# EVK-IRIS-W1-FTDI.net
KiCad netlist of a schematic drawn in Altium Designer
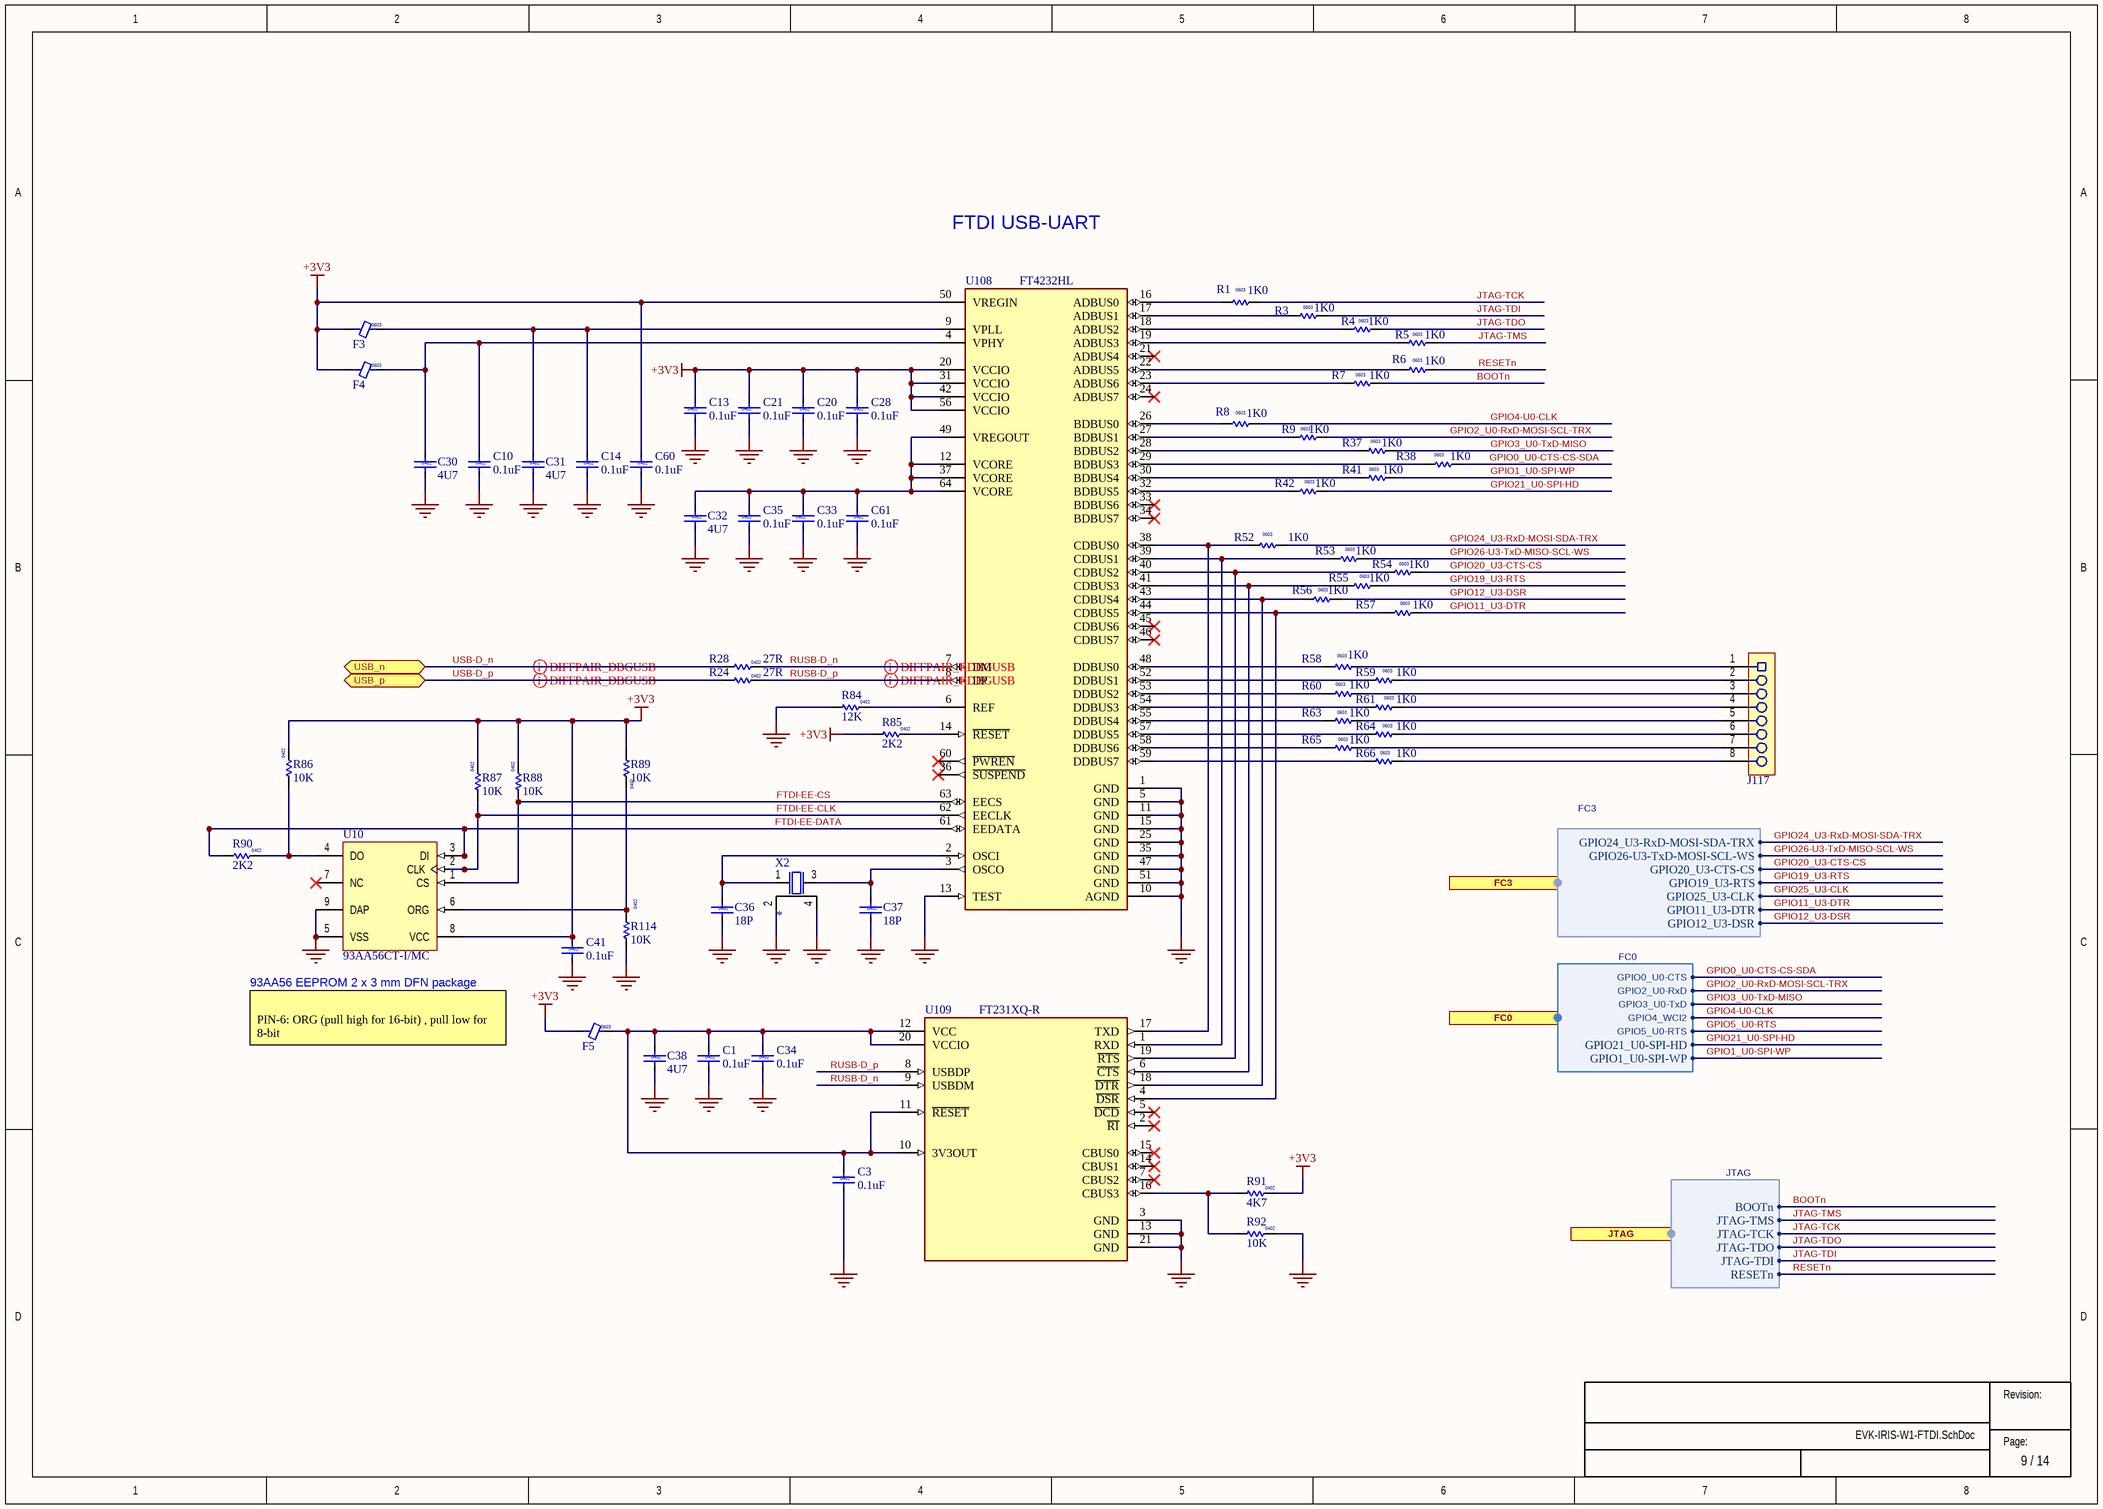
[diagram p0: EVK-IRIS-W1-FTDI.SchDoc]

(export (version "E")
  (design (tool "Eeschema 10.0.6"))
  (components
    (comp (ref "C1")
      (value "0.1uF")
      (footprint "Cap 0402 HD")
      (description "Cap, Ceramic 0.1uF 10V 10% X5R 0402")
      (fields
        (field (name "SIZE") "0402")
        (field (name "PART NUMBER") "120-00016")
        (field (name "TOLERANCE") "+/- 10%")
      )
      (libsource (lib "Arena_Parts_DB_Lib") (part "Cap Chip"))
    )
    (comp (ref "C3")
      (value "0.1uF")
      (footprint "Cap 0402 HD")
      (description "Cap, Ceramic 0.1uF 10V 10% X5R 0402")
      (fields
        (field (name "SIZE") "0402")
        (field (name "PART NUMBER") "120-00016")
        (field (name "TOLERANCE") "+/- 10%")
      )
      (libsource (lib "Arena_Parts_DB_Lib") (part "Cap Chip"))
    )
    (comp (ref "C10")
      (value "0.1uF")
      (footprint "Cap 0402 HD")
      (description "Cap, Ceramic 0.1uF 10V 10% X5R 0402")
      (fields
        (field (name "SIZE") "0402")
        (field (name "PART NUMBER") "120-00016")
        (field (name "TOLERANCE") "+/- 10%")
      )
      (libsource (lib "Arena_Parts_DB_Lib") (part "Cap Chip"))
    )
    (comp (ref "C13")
      (value "0.1uF")
      (footprint "Cap 0402 HD")
      (description "Cap, Ceramic 0.1uF 10V 10% X5R 0402")
      (fields
        (field (name "SIZE") "0402")
        (field (name "PART NUMBER") "120-00016")
        (field (name "TOLERANCE") "+/- 10%")
      )
      (libsource (lib "Arena_Parts_DB_Lib") (part "Cap Chip"))
    )
    (comp (ref "C14")
      (value "0.1uF")
      (footprint "Cap 0402 HD")
      (description "Cap, Ceramic 0.1uF 10V 10% X5R 0402")
      (fields
        (field (name "SIZE") "0402")
        (field (name "PART NUMBER") "120-00016")
        (field (name "TOLERANCE") "+/- 10%")
      )
      (libsource (lib "Arena_Parts_DB_Lib") (part "Cap Chip"))
    )
    (comp (ref "C20")
      (value "0.1uF")
      (footprint "Cap 0402 HD")
      (description "Cap, Ceramic 0.1uF 10V 10% X5R 0402")
      (fields
        (field (name "SIZE") "0402")
        (field (name "PART NUMBER") "120-00016")
        (field (name "TOLERANCE") "+/- 10%")
      )
      (libsource (lib "Arena_Parts_DB_Lib") (part "Cap Chip"))
    )
    (comp (ref "C21")
      (value "0.1uF")
      (footprint "Cap 0402 HD")
      (description "Cap, Ceramic 0.1uF 10V 10% X5R 0402")
      (fields
        (field (name "SIZE") "0402")
        (field (name "PART NUMBER") "120-00016")
        (field (name "TOLERANCE") "+/- 10%")
      )
      (libsource (lib "Arena_Parts_DB_Lib") (part "Cap Chip"))
    )
    (comp (ref "C28")
      (value "0.1uF")
      (footprint "Cap 0402 HD")
      (description "Cap, Ceramic 0.1uF 10V 10% X5R 0402")
      (fields
        (field (name "SIZE") "0402")
        (field (name "PART NUMBER") "120-00016")
        (field (name "TOLERANCE") "+/- 10%")
      )
      (libsource (lib "Arena_Parts_DB_Lib") (part "Cap Chip"))
    )
    (comp (ref "C30")
      (value "4U7")
      (footprint "Cap 0402 HD")
      (description "CAP CER X5R 0402 4U7 20% 10V")
      (fields
        (field (name "SIZE") "0402")
        (field (name "PART NUMBER") "UBXH01-0000243")
        (field (name "TOLERANCE") "20%")
        (field (name "EDITOR") "martin.pilik")
        (field (name "RELEASED BY") "fabrice.bret-dibat")
      )
      (libsource (lib "UBX_Parts_DB_Lib") (part "Cap Chip"))
    )
    (comp (ref "C31")
      (value "4U7")
      (footprint "Cap 0402 HD")
      (description "CAP CER X5R 0402 4U7 20% 10V")
      (fields
        (field (name "SIZE") "0402")
        (field (name "PART NUMBER") "UBXH01-0000243")
        (field (name "TOLERANCE") "20%")
        (field (name "EDITOR") "martin.pilik")
        (field (name "RELEASED BY") "fabrice.bret-dibat")
      )
      (libsource (lib "UBX_Parts_DB_Lib") (part "Cap Chip"))
    )
    (comp (ref "C32")
      (value "4U7")
      (footprint "Cap 0402 HD")
      (description "CAP CER X5R 0402 4U7 20% 10V")
      (fields
        (field (name "SIZE") "0402")
        (field (name "PART NUMBER") "UBXH01-0000243")
        (field (name "TOLERANCE") "20%")
        (field (name "EDITOR") "martin.pilik")
        (field (name "RELEASED BY") "fabrice.bret-dibat")
      )
      (libsource (lib "UBX_Parts_DB_Lib") (part "Cap Chip"))
    )
    (comp (ref "C33")
      (value "0.1uF")
      (footprint "Cap 0402 HD")
      (description "Cap, Ceramic 0.1uF 10V 10% X5R 0402")
      (fields
        (field (name "SIZE") "0402")
        (field (name "PART NUMBER") "120-00016")
        (field (name "TOLERANCE") "+/- 10%")
      )
      (libsource (lib "Arena_Parts_DB_Lib") (part "Cap Chip"))
    )
    (comp (ref "C34")
      (value "0.1uF")
      (footprint "Cap 0402 HD")
      (description "Cap, Ceramic 0.1uF 10V 10% X5R 0402")
      (fields
        (field (name "SIZE") "0402")
        (field (name "PART NUMBER") "120-00016")
        (field (name "TOLERANCE") "+/- 10%")
      )
      (libsource (lib "Arena_Parts_DB_Lib") (part "Cap Chip"))
    )
    (comp (ref "C35")
      (value "0.1uF")
      (footprint "Cap 0402 HD")
      (description "Cap, Ceramic 0.1uF 10V 10% X5R 0402")
      (fields
        (field (name "SIZE") "0402")
        (field (name "PART NUMBER") "120-00016")
        (field (name "TOLERANCE") "+/- 10%")
      )
      (libsource (lib "Arena_Parts_DB_Lib") (part "Cap Chip"))
    )
    (comp (ref "C36")
      (value "18P")
      (footprint "Cap 0402")
      (description "CAP CER C0G 0402 18P 5% 25V")
      (fields
        (field (name "SIZE") "0402")
        (field (name "PART NUMBER") "UBXH01-0004017")
        (field (name "TOLERANCE") "5%")
        (field (name "EDITOR") "doris.zahnd")
        (field (name "RELEASED BY") "daniel.hurni")
      )
      (libsource (lib "UBX_Parts_DB_Lib") (part "Cap Chip"))
    )
    (comp (ref "C37")
      (value "18P")
      (footprint "Cap 0402")
      (description "CAP CER C0G 0402 18P 5% 25V")
      (fields
        (field (name "SIZE") "0402")
        (field (name "PART NUMBER") "UBXH01-0004017")
        (field (name "TOLERANCE") "5%")
        (field (name "EDITOR") "doris.zahnd")
        (field (name "RELEASED BY") "daniel.hurni")
      )
      (libsource (lib "UBX_Parts_DB_Lib") (part "Cap Chip"))
    )
    (comp (ref "C38")
      (value "4U7")
      (footprint "Cap 0402 HD")
      (description "CAP CER X5R 0402 4U7 20% 10V")
      (fields
        (field (name "SIZE") "0402")
        (field (name "PART NUMBER") "UBXH01-0000243")
        (field (name "TOLERANCE") "20%")
        (field (name "EDITOR") "martin.pilik")
        (field (name "RELEASED BY") "fabrice.bret-dibat")
      )
      (libsource (lib "UBX_Parts_DB_Lib") (part "Cap Chip"))
    )
    (comp (ref "C41")
      (value "0.1uF")
      (footprint "Cap 0402 HD")
      (description "Cap, Ceramic 0.1uF 10V 10% X5R 0402")
      (fields
        (field (name "SIZE") "0402")
        (field (name "PART NUMBER") "120-00016")
        (field (name "TOLERANCE") "+/- 10%")
      )
      (libsource (lib "Arena_Parts_DB_Lib") (part "Cap Chip"))
    )
    (comp (ref "C60")
      (value "0.1uF")
      (footprint "Cap 0402 HD")
      (description "Cap, Ceramic 0.1uF 10V 10% X5R 0402")
      (fields
        (field (name "SIZE") "0402")
        (field (name "PART NUMBER") "120-00016")
        (field (name "TOLERANCE") "+/- 10%")
      )
      (libsource (lib "Arena_Parts_DB_Lib") (part "Cap Chip"))
    )
    (comp (ref "C61")
      (value "0.1uF")
      (footprint "Cap 0402 HD")
      (description "Cap, Ceramic 0.1uF 10V 10% X5R 0402")
      (fields
        (field (name "SIZE") "0402")
        (field (name "PART NUMBER") "120-00016")
        (field (name "TOLERANCE") "+/- 10%")
      )
      (libsource (lib "Arena_Parts_DB_Lib") (part "Cap Chip"))
    )
    (comp (ref "F3")
      (value "UBXH08-0000001")
      (footprint "IND 0603 HD")
      (description "FERRITE BEAD 0603 600 OHM AT 100MHZ 600OHM 500mA")
      (fields
        (field (name "SIZE") "0603")
        (field (name "MANUFACTURER") "TDK Corporation")
        (field (name "EDITOR") "daniel.hurni")
        (field (name "RELEASED BY") "martin.frauchiger")
      )
      (libsource (lib "UBX_Parts_DB_Lib") (part "FB sm"))
    )
    (comp (ref "F4")
      (value "UBXH08-0000001")
      (footprint "IND 0603 HD")
      (description "FERRITE BEAD 0603 600 OHM AT 100MHZ 600OHM 500mA")
      (fields
        (field (name "SIZE") "0603")
        (field (name "MANUFACTURER") "TDK Corporation")
        (field (name "EDITOR") "daniel.hurni")
        (field (name "RELEASED BY") "martin.frauchiger")
      )
      (libsource (lib "UBX_Parts_DB_Lib") (part "FB sm"))
    )
    (comp (ref "F5")
      (value "UBXH08-0000001")
      (footprint "IND 0603 HD")
      (description "FERRITE BEAD 0603 600 OHM AT 100MHZ 600OHM 500mA")
      (fields
        (field (name "SIZE") "0603")
        (field (name "MANUFACTURER") "TDK Corporation")
        (field (name "EDITOR") "daniel.hurni")
        (field (name "RELEASED BY") "martin.frauchiger")
      )
      (libsource (lib "UBX_Parts_DB_Lib") (part "FB sm"))
    )
    (comp (ref "J117")
      (value "130-00102")
      (footprint "SKT-0.1P-SSM-108-L-SV")
      (description "Socket Strip 0.1\" 8 Pin 1Row SMD Black")
      (fields (field (name "VOLTAGE") "572VDC"))
      (libsource (lib "Arena_Parts_DB_Lib") (part "CON-8Pin_1Row"))
    )
    (comp (ref "R1")
      (value "1K0")
      (footprint "RES 0603 HD")
      (description "RES THICK FILM CHIP 0603 25PPM 1K0 0.1% 100mW")
      (fields
        (field (name "SIZE") "0603")
        (field (name "PART NUMBER") "UBXH18-0000400")
        (field (name "TOLERANCE") "0.1%")
        (field (name "EDITOR") "martin.kessel")
      )
      (libsource (lib "UBX_Parts_DB_Lib") (part "Res sm"))
    )
    (comp (ref "R3")
      (value "1K0")
      (footprint "RES 0603 HD")
      (description "RES THICK FILM CHIP 0603 25PPM 1K0 0.1% 100mW")
      (fields
        (field (name "SIZE") "0603")
        (field (name "PART NUMBER") "UBXH18-0000400")
        (field (name "TOLERANCE") "0.1%")
        (field (name "EDITOR") "martin.kessel")
      )
      (libsource (lib "UBX_Parts_DB_Lib") (part "Res sm"))
    )
    (comp (ref "R4")
      (value "1K0")
      (footprint "RES 0603 HD")
      (description "RES THICK FILM CHIP 0603 25PPM 1K0 0.1% 100mW")
      (fields
        (field (name "SIZE") "0603")
        (field (name "PART NUMBER") "UBXH18-0000400")
        (field (name "TOLERANCE") "0.1%")
        (field (name "EDITOR") "martin.kessel")
      )
      (libsource (lib "UBX_Parts_DB_Lib") (part "Res sm"))
    )
    (comp (ref "R5")
      (value "1K0")
      (footprint "RES 0603 HD")
      (description "RES THICK FILM CHIP 0603 25PPM 1K0 0.1% 100mW")
      (fields
        (field (name "SIZE") "0603")
        (field (name "PART NUMBER") "UBXH18-0000400")
        (field (name "TOLERANCE") "0.1%")
        (field (name "EDITOR") "martin.kessel")
      )
      (libsource (lib "UBX_Parts_DB_Lib") (part "Res sm"))
    )
    (comp (ref "R6")
      (value "1K0")
      (footprint "RES 0603 HD")
      (description "RES THICK FILM CHIP 0603 25PPM 1K0 0.1% 100mW")
      (fields
        (field (name "SIZE") "0603")
        (field (name "PART NUMBER") "UBXH18-0000400")
        (field (name "TOLERANCE") "0.1%")
        (field (name "EDITOR") "martin.kessel")
      )
      (libsource (lib "UBX_Parts_DB_Lib") (part "Res sm"))
    )
    (comp (ref "R7")
      (value "1K0")
      (footprint "RES 0603 HD")
      (description "RES THICK FILM CHIP 0603 25PPM 1K0 0.1% 100mW")
      (fields
        (field (name "SIZE") "0603")
        (field (name "PART NUMBER") "UBXH18-0000400")
        (field (name "TOLERANCE") "0.1%")
        (field (name "EDITOR") "martin.kessel")
      )
      (libsource (lib "UBX_Parts_DB_Lib") (part "Res sm"))
    )
    (comp (ref "R8")
      (value "1K0")
      (footprint "RES 0603 HD")
      (description "RES THICK FILM CHIP 0603 25PPM 1K0 0.1% 100mW")
      (fields
        (field (name "SIZE") "0603")
        (field (name "PART NUMBER") "UBXH18-0000400")
        (field (name "TOLERANCE") "0.1%")
        (field (name "EDITOR") "martin.kessel")
      )
      (libsource (lib "UBX_Parts_DB_Lib") (part "Res sm"))
    )
    (comp (ref "R9")
      (value "1K0")
      (footprint "RES 0603 HD")
      (description "RES THICK FILM CHIP 0603 25PPM 1K0 0.1% 100mW")
      (fields
        (field (name "SIZE") "0603")
        (field (name "PART NUMBER") "UBXH18-0000400")
        (field (name "TOLERANCE") "0.1%")
        (field (name "EDITOR") "martin.kessel")
      )
      (libsource (lib "UBX_Parts_DB_Lib") (part "Res sm"))
    )
    (comp (ref "R24")
      (value "27R")
      (footprint "RES 0402 HD")
      (description "Resistor, 27ohm, 1%, 1/16W, 0402")
      (fields
        (field (name "SIZE") "0402")
        (field (name "PART NUMBER") "180-00125")
        (field (name "POWER") "1/16W")
      )
      (libsource (lib "Arena_Parts_DB_Lib") (part "Res sm"))
    )
    (comp (ref "R28")
      (value "27R")
      (footprint "RES 0402 HD")
      (description "Resistor, 27ohm, 1%, 1/16W, 0402")
      (fields
        (field (name "SIZE") "0402")
        (field (name "PART NUMBER") "180-00125")
        (field (name "POWER") "1/16W")
      )
      (libsource (lib "Arena_Parts_DB_Lib") (part "Res sm"))
    )
    (comp (ref "R37")
      (value "1K0")
      (footprint "RES 0603 HD")
      (description "RES THICK FILM CHIP 0603 25PPM 1K0 0.1% 100mW")
      (fields
        (field (name "SIZE") "0603")
        (field (name "PART NUMBER") "UBXH18-0000400")
        (field (name "TOLERANCE") "0.1%")
        (field (name "EDITOR") "martin.kessel")
      )
      (libsource (lib "UBX_Parts_DB_Lib") (part "Res sm"))
    )
    (comp (ref "R38")
      (value "1K0")
      (footprint "RES 0603 HD")
      (description "RES THICK FILM CHIP 0603 25PPM 1K0 0.1% 100mW")
      (fields
        (field (name "SIZE") "0603")
        (field (name "PART NUMBER") "UBXH18-0000400")
        (field (name "TOLERANCE") "0.1%")
        (field (name "EDITOR") "martin.kessel")
      )
      (libsource (lib "UBX_Parts_DB_Lib") (part "Res sm"))
    )
    (comp (ref "R41")
      (value "1K0")
      (footprint "RES 0603 HD")
      (description "RES THICK FILM CHIP 0603 25PPM 1K0 0.1% 100mW")
      (fields
        (field (name "SIZE") "0603")
        (field (name "PART NUMBER") "UBXH18-0000400")
        (field (name "TOLERANCE") "0.1%")
        (field (name "EDITOR") "martin.kessel")
      )
      (libsource (lib "UBX_Parts_DB_Lib") (part "Res sm"))
    )
    (comp (ref "R42")
      (value "1K0")
      (footprint "RES 0603 HD")
      (description "RES THICK FILM CHIP 0603 25PPM 1K0 0.1% 100mW")
      (fields
        (field (name "SIZE") "0603")
        (field (name "PART NUMBER") "UBXH18-0000400")
        (field (name "TOLERANCE") "0.1%")
        (field (name "EDITOR") "martin.kessel")
      )
      (libsource (lib "UBX_Parts_DB_Lib") (part "Res sm"))
    )
    (comp (ref "R52")
      (value "1K0")
      (footprint "RES 0603 HD")
      (description "RES THICK FILM CHIP 0603 25PPM 1K0 0.1% 100mW")
      (fields
        (field (name "SIZE") "0603")
        (field (name "PART NUMBER") "UBXH18-0000400")
        (field (name "TOLERANCE") "0.1%")
        (field (name "EDITOR") "martin.kessel")
      )
      (libsource (lib "UBX_Parts_DB_Lib") (part "Res sm"))
    )
    (comp (ref "R53")
      (value "1K0")
      (footprint "RES 0603 HD")
      (description "RES THICK FILM CHIP 0603 25PPM 1K0 0.1% 100mW")
      (fields
        (field (name "SIZE") "0603")
        (field (name "PART NUMBER") "UBXH18-0000400")
        (field (name "TOLERANCE") "0.1%")
        (field (name "EDITOR") "martin.kessel")
      )
      (libsource (lib "UBX_Parts_DB_Lib") (part "Res sm"))
    )
    (comp (ref "R54")
      (value "1K0")
      (footprint "RES 0603 HD")
      (description "RES THICK FILM CHIP 0603 25PPM 1K0 0.1% 100mW")
      (fields
        (field (name "SIZE") "0603")
        (field (name "PART NUMBER") "UBXH18-0000400")
        (field (name "TOLERANCE") "0.1%")
        (field (name "EDITOR") "martin.kessel")
      )
      (libsource (lib "UBX_Parts_DB_Lib") (part "Res sm"))
    )
    (comp (ref "R55")
      (value "1K0")
      (footprint "RES 0603 HD")
      (description "RES THICK FILM CHIP 0603 25PPM 1K0 0.1% 100mW")
      (fields
        (field (name "SIZE") "0603")
        (field (name "PART NUMBER") "UBXH18-0000400")
        (field (name "TOLERANCE") "0.1%")
        (field (name "EDITOR") "martin.kessel")
      )
      (libsource (lib "UBX_Parts_DB_Lib") (part "Res sm"))
    )
    (comp (ref "R56")
      (value "1K0")
      (footprint "RES 0603 HD")
      (description "RES THICK FILM CHIP 0603 25PPM 1K0 0.1% 100mW")
      (fields
        (field (name "SIZE") "0603")
        (field (name "PART NUMBER") "UBXH18-0000400")
        (field (name "TOLERANCE") "0.1%")
        (field (name "EDITOR") "martin.kessel")
      )
      (libsource (lib "UBX_Parts_DB_Lib") (part "Res sm"))
    )
    (comp (ref "R57")
      (value "1K0")
      (footprint "RES 0603 HD")
      (description "RES THICK FILM CHIP 0603 25PPM 1K0 0.1% 100mW")
      (fields
        (field (name "SIZE") "0603")
        (field (name "PART NUMBER") "UBXH18-0000400")
        (field (name "TOLERANCE") "0.1%")
        (field (name "EDITOR") "martin.kessel")
      )
      (libsource (lib "UBX_Parts_DB_Lib") (part "Res sm"))
    )
    (comp (ref "R58")
      (value "1K0")
      (footprint "RES 0603 HD")
      (description "RES THICK FILM CHIP 0603 25PPM 1K0 0.1% 100mW")
      (fields
        (field (name "SIZE") "0603")
        (field (name "PART NUMBER") "UBXH18-0000400")
        (field (name "TOLERANCE") "0.1%")
        (field (name "EDITOR") "martin.kessel")
      )
      (libsource (lib "UBX_Parts_DB_Lib") (part "Res sm"))
    )
    (comp (ref "R59")
      (value "1K0")
      (footprint "RES 0603 HD")
      (description "RES THICK FILM CHIP 0603 25PPM 1K0 0.1% 100mW")
      (fields
        (field (name "SIZE") "0603")
        (field (name "PART NUMBER") "UBXH18-0000400")
        (field (name "TOLERANCE") "0.1%")
        (field (name "EDITOR") "martin.kessel")
      )
      (libsource (lib "UBX_Parts_DB_Lib") (part "Res sm"))
    )
    (comp (ref "R60")
      (value "1K0")
      (footprint "RES 0603 HD")
      (description "RES THICK FILM CHIP 0603 25PPM 1K0 0.1% 100mW")
      (fields
        (field (name "SIZE") "0603")
        (field (name "PART NUMBER") "UBXH18-0000400")
        (field (name "TOLERANCE") "0.1%")
        (field (name "EDITOR") "martin.kessel")
      )
      (libsource (lib "UBX_Parts_DB_Lib") (part "Res sm"))
    )
    (comp (ref "R61")
      (value "1K0")
      (footprint "RES 0603 HD")
      (description "RES THICK FILM CHIP 0603 25PPM 1K0 0.1% 100mW")
      (fields
        (field (name "SIZE") "0603")
        (field (name "PART NUMBER") "UBXH18-0000400")
        (field (name "TOLERANCE") "0.1%")
        (field (name "EDITOR") "martin.kessel")
      )
      (libsource (lib "UBX_Parts_DB_Lib") (part "Res sm"))
    )
    (comp (ref "R63")
      (value "1K0")
      (footprint "RES 0603 HD")
      (description "RES THICK FILM CHIP 0603 25PPM 1K0 0.1% 100mW")
      (fields
        (field (name "SIZE") "0603")
        (field (name "PART NUMBER") "UBXH18-0000400")
        (field (name "TOLERANCE") "0.1%")
        (field (name "EDITOR") "martin.kessel")
      )
      (libsource (lib "UBX_Parts_DB_Lib") (part "Res sm"))
    )
    (comp (ref "R64")
      (value "1K0")
      (footprint "RES 0603 HD")
      (description "RES THICK FILM CHIP 0603 25PPM 1K0 0.1% 100mW")
      (fields
        (field (name "SIZE") "0603")
        (field (name "PART NUMBER") "UBXH18-0000400")
        (field (name "TOLERANCE") "0.1%")
        (field (name "EDITOR") "martin.kessel")
      )
      (libsource (lib "UBX_Parts_DB_Lib") (part "Res sm"))
    )
    (comp (ref "R65")
      (value "1K0")
      (footprint "RES 0603 HD")
      (description "RES THICK FILM CHIP 0603 25PPM 1K0 0.1% 100mW")
      (fields
        (field (name "SIZE") "0603")
        (field (name "PART NUMBER") "UBXH18-0000400")
        (field (name "TOLERANCE") "0.1%")
        (field (name "EDITOR") "martin.kessel")
      )
      (libsource (lib "UBX_Parts_DB_Lib") (part "Res sm"))
    )
    (comp (ref "R66")
      (value "1K0")
      (footprint "RES 0603 HD")
      (description "RES THICK FILM CHIP 0603 25PPM 1K0 0.1% 100mW")
      (fields
        (field (name "SIZE") "0603")
        (field (name "PART NUMBER") "UBXH18-0000400")
        (field (name "TOLERANCE") "0.1%")
        (field (name "EDITOR") "martin.kessel")
      )
      (libsource (lib "UBX_Parts_DB_Lib") (part "Res sm"))
    )
    (comp (ref "R84")
      (value "12K")
      (footprint "RES 0402 HD")
      (description "RES THICK FILM CHIP 0402 12K 1% 63mW")
      (fields
        (field (name "SIZE") "0402")
        (field (name "PART NUMBER") "UBXH18-0000137")
        (field (name "TOLERANCE") "1%")
        (field (name "EDITOR") "matej.budin")
        (field (name "RELEASED BY") "gabriele.capello")
      )
      (libsource (lib "UBX_Parts_DB_Lib") (part "Res sm"))
    )
    (comp (ref "R85")
      (value "2K2")
      (footprint "RES 0402 HD")
      (description "RES THICK FILM CHIP 0402 2K2 5% 100mW")
      (fields
        (field (name "SIZE") "0402")
        (field (name "PART NUMBER") "UBXH18-0008057")
        (field (name "TOLERANCE") "5%")
        (field (name "EDITOR") "roland.rust")
        (field (name "RELEASED BY") "roland.rust")
      )
      (libsource (lib "UBX_Parts_DB_Lib") (part "Res sm"))
    )
    (comp (ref "R86")
      (value "10K")
      (footprint "RES 0402 HD")
      (description "RES THICK FILM CHIP 0402 10K 5% 100mW")
      (fields
        (field (name "SIZE") "0402")
        (field (name "PART NUMBER") "UBXH18-0008073")
        (field (name "TOLERANCE") "5%")
        (field (name "EDITOR") "martin.frauchiger")
        (field (name "RELEASED BY") "martin.frauchiger")
      )
      (libsource (lib "UBX_Parts_DB_Lib") (part "Res sm"))
    )
    (comp (ref "R87")
      (value "10K")
      (footprint "RES 0402 HD")
      (description "RES THICK FILM CHIP 0402 10K 5% 100mW")
      (fields
        (field (name "SIZE") "0402")
        (field (name "PART NUMBER") "UBXH18-0008073")
        (field (name "TOLERANCE") "5%")
        (field (name "EDITOR") "martin.frauchiger")
        (field (name "RELEASED BY") "martin.frauchiger")
      )
      (libsource (lib "UBX_Parts_DB_Lib") (part "Res sm"))
    )
    (comp (ref "R88")
      (value "10K")
      (footprint "RES 0402 HD")
      (description "RES THICK FILM CHIP 0402 10K 5% 100mW")
      (fields
        (field (name "SIZE") "0402")
        (field (name "PART NUMBER") "UBXH18-0008073")
        (field (name "TOLERANCE") "5%")
        (field (name "EDITOR") "martin.frauchiger")
        (field (name "RELEASED BY") "martin.frauchiger")
      )
      (libsource (lib "UBX_Parts_DB_Lib") (part "Res sm"))
    )
    (comp (ref "R89")
      (value "10K")
      (footprint "RES 0402 HD")
      (description "RES THICK FILM CHIP 0402 10K 5% 100mW")
      (fields
        (field (name "SIZE") "0402")
        (field (name "PART NUMBER") "UBXH18-0008073")
        (field (name "TOLERANCE") "5%")
        (field (name "EDITOR") "martin.frauchiger")
        (field (name "RELEASED BY") "martin.frauchiger")
      )
      (libsource (lib "UBX_Parts_DB_Lib") (part "Res sm"))
    )
    (comp (ref "R90")
      (value "2K2")
      (footprint "RES 0402 HD")
      (description "RES THICK FILM CHIP 0402 2K2 5% 100mW")
      (fields
        (field (name "SIZE") "0402")
        (field (name "PART NUMBER") "UBXH18-0008057")
        (field (name "TOLERANCE") "5%")
        (field (name "EDITOR") "roland.rust")
        (field (name "RELEASED BY") "roland.rust")
      )
      (libsource (lib "UBX_Parts_DB_Lib") (part "Res sm"))
    )
    (comp (ref "R91")
      (value "4K7")
      (footprint "RES 0402 HD")
      (description "RES THICK FILM CHIP 0402 4K7 5% 100mW")
      (fields
        (field (name "SIZE") "0402")
        (field (name "PART NUMBER") "UBXH18-0008065")
        (field (name "TOLERANCE") "5%")
        (field (name "EDITOR") "martin.frauchiger")
        (field (name "RELEASED BY") "martin.frauchiger")
      )
      (libsource (lib "UBX_Parts_DB_Lib") (part "Res sm"))
    )
    (comp (ref "R92")
      (value "10K")
      (footprint "RES 0402 HD")
      (description "RES THICK FILM CHIP 0402 10K 5% 100mW")
      (fields
        (field (name "SIZE") "0402")
        (field (name "PART NUMBER") "UBXH18-0008073")
        (field (name "TOLERANCE") "5%")
        (field (name "EDITOR") "martin.frauchiger")
        (field (name "RELEASED BY") "martin.frauchiger")
      )
      (libsource (lib "UBX_Parts_DB_Lib") (part "Res sm"))
    )
    (comp (ref "R114")
      (value "10K")
      (footprint "RES 0402 HD")
      (description "RES THICK FILM CHIP 0402 10K 5% 100mW")
      (fields
        (field (name "SIZE") "0402")
        (field (name "PART NUMBER") "UBXH18-0008073")
        (field (name "TOLERANCE") "5%")
        (field (name "EDITOR") "martin.frauchiger")
        (field (name "RELEASED BY") "martin.frauchiger")
      )
      (libsource (lib "UBX_Parts_DB_Lib") (part "Res sm"))
    )
    (comp (ref "U10")
      (value "93AA56CT-I/MC")
      (footprint "DFN-MC8")
      (fields (field (name "MANUFACTURER") "Microchip"))
      (libsource (lib "93AA56CT-I") (part "MEM-SEEPROM-93AA46C-MC-9"))
    )
    (comp (ref "U108")
      (value "FT4232HL")
      (footprint "QFP0.5P16x16-64Pin_HD")
      (description "FTDI FT4232HL QUAD HIGH SPEED USB TO MULTIPURPOSE UART LQFP-64")
      (fields
        (field (name "PART NUMBER") "UBXH10-0000092")
        (field (name "MANUFACTURER") "FTDI Future Technology Devices International")
        (field (name "EDITOR") "olof.viklund")
        (field (name "RELEASED BY") "aneeb.sohail")
      )
      (libsource (lib "UBX_Parts_DB_Lib") (part "FT4232HL"))
    )
    (comp (ref "U109")
      (value "FT231XQ-R")
      (footprint "QFN_5x5_FT231XQ")
      (description "FTDI USB TO SERIAL FULL UART INTERFACE QFN20")
      (fields
        (field (name "PART NUMBER") "UBXH10-0000054")
        (field (name "MANUFACTURER") "FTDI Future Technology Devices International")
        (field (name "EDITOR") "adam.johansson")
        (field (name "RELEASED BY") "jaka.bevk")
      )
      (libsource (lib "UBX_Parts_DB_Lib") (part "FT231XQ-R"))
    )
    (comp (ref "X2")
      (value "100-00006")
      (footprint "XTAL_3225")
      (description "XTAL, 4Pin, 12.0000MHz, 18pF, 20ppm, 4Pins")
      (fields (field (name "ALTIUM_VALUE") "*") (field (name "VOLTAGE") "None"))
      (libsource (lib "Arena_Parts_DB_Lib") (part "XTAL_4Pin"))
    )
  )
  (nets
    (net (code "4") (name "+3V3") (class "Default")
      (node (ref "C13") (pin "1") (pinfunction "1_1") (pintype "passive"))
      (node (ref "C20") (pin "1") (pinfunction "1_1") (pintype "passive"))
      (node (ref "C21") (pin "1") (pinfunction "1_1") (pintype "passive"))
      (node (ref "C28") (pin "1") (pinfunction "1_1") (pintype "passive"))
      (node (ref "C41") (pin "1") (pinfunction "1_1") (pintype "passive"))
      (node (ref "C60") (pin "1") (pinfunction "1_1") (pintype "passive"))
      (node (ref "F3") (pin "1") (pinfunction "1_1") (pintype "passive"))
      (node (ref "F4") (pin "1") (pinfunction "1_1") (pintype "passive"))
      (node (ref "F5") (pin "1") (pinfunction "1_1") (pintype "passive"))
      (node (ref "R85") (pin "1") (pinfunction "1_1") (pintype "passive"))
      (node (ref "R86") (pin "2") (pinfunction "2_2") (pintype "passive"))
      (node (ref "R87") (pin "2") (pinfunction "2_2") (pintype "passive"))
      (node (ref "R88") (pin "2") (pinfunction "2_2") (pintype "passive"))
      (node (ref "R89") (pin "1") (pinfunction "1_1") (pintype "passive"))
      (node (ref "R91") (pin "2") (pinfunction "2_2") (pintype "passive"))
      (node (ref "U10") (pin "8") (pinfunction "VCC_8") (pintype "power_in"))
      (node (ref "U108") (pin "20") (pinfunction "VCCIO_20") (pintype "power_in"))
      (node (ref "U108") (pin "31") (pinfunction "VCCIO_31") (pintype "power_in"))
      (node (ref "U108") (pin "42") (pinfunction "VCCIO_42") (pintype "power_in"))
      (node (ref "U108") (pin "50") (pinfunction "VREGIN_50") (pintype "power_in"))
      (node (ref "U108") (pin "56") (pinfunction "VCCIO_56") (pintype "power_in"))
    )
    (net (code "5") (name "/BOOTn") (class "Default")
      (node (ref "R7") (pin "2") (pinfunction "2_2") (pintype "passive"))
    )
    (net (code "6") (name "/FTDI-EE-CLK") (class "Default")
      (node (ref "R87") (pin "1") (pinfunction "1_1") (pintype "passive"))
      (node (ref "U10") (pin "2") (pinfunction "CLK_2") (pintype "input"))
      (node (ref "U108") (pin "62") (pinfunction "EECLK_62") (pintype "output"))
    )
    (net (code "7") (name "/FTDI-EE-CS") (class "Default")
      (node (ref "R88") (pin "1") (pinfunction "1_1") (pintype "passive"))
      (node (ref "U10") (pin "1") (pinfunction "CS_1") (pintype "input"))
      (node (ref "U108") (pin "63") (pinfunction "EECS_63") (pintype "bidirectional"))
    )
    (net (code "8") (name "/FTDI-EE-DATA") (class "Default")
      (node (ref "R90") (pin "1") (pinfunction "1_1") (pintype "passive"))
      (node (ref "U10") (pin "3") (pinfunction "DI_3") (pintype "input"))
      (node (ref "U108") (pin "61") (pinfunction "EEDATA_61") (pintype "bidirectional"))
    )
    (net (code "9") (name "/GPIO0_U0-CTS-CS-SDA") (class "Default")
      (node (ref "R38") (pin "2") (pinfunction "2_2") (pintype "passive"))
    )
    (net (code "10") (name "/GPIO1_U0-SPI-WP") (class "Default")
      (node (ref "R41") (pin "2") (pinfunction "2_2") (pintype "passive"))
    )
    (net (code "11") (name "/GPIO2_U0-RxD-MOSI-SCL-TRX") (class "Default")
      (node (ref "R9") (pin "2") (pinfunction "2_2") (pintype "passive"))
    )
    (net (code "12") (name "/GPIO3_U0-TxD-MISO") (class "Default")
      (node (ref "R37") (pin "2") (pinfunction "2_2") (pintype "passive"))
    )
    (net (code "13") (name "/GPIO4-U0-CLK") (class "Default")
      (node (ref "R8") (pin "2") (pinfunction "2_2") (pintype "passive"))
    )
    (net (code "15") (name "/GPIO11_U3-DTR") (class "Default")
      (node (ref "R57") (pin "2") (pinfunction "2_2") (pintype "passive"))
    )
    (net (code "16") (name "/GPIO12_U3-DSR") (class "Default")
      (node (ref "R56") (pin "2") (pinfunction "2_2") (pintype "passive"))
    )
    (net (code "17") (name "/GPIO19_U3-RTS") (class "Default")
      (node (ref "R55") (pin "2") (pinfunction "2_2") (pintype "passive"))
    )
    (net (code "18") (name "/GPIO20_U3-CTS-CS") (class "Default")
      (node (ref "R54") (pin "2") (pinfunction "2_2") (pintype "passive"))
    )
    (net (code "19") (name "/GPIO21_U0-SPI-HD") (class "Default")
      (node (ref "R42") (pin "2") (pinfunction "2_2") (pintype "passive"))
    )
    (net (code "20") (name "/GPIO24_U3-RxD-MOSI-SDA-TRX") (class "Default")
      (node (ref "R52") (pin "2") (pinfunction "2_2") (pintype "passive"))
    )
    (net (code "22") (name "/GPIO26-U3-TxD-MISO-SCL-WS") (class "Default")
      (node (ref "R53") (pin "2") (pinfunction "2_2") (pintype "passive"))
    )
    (net (code "23") (name "/JTAG-TCK") (class "Default")
      (node (ref "R1") (pin "2") (pinfunction "2_2") (pintype "passive"))
    )
    (net (code "24") (name "/JTAG-TDI") (class "Default")
      (node (ref "R3") (pin "2") (pinfunction "2_2") (pintype "passive"))
    )
    (net (code "25") (name "/JTAG-TDO") (class "Default")
      (node (ref "R4") (pin "2") (pinfunction "2_2") (pintype "passive"))
    )
    (net (code "26") (name "/JTAG-TMS") (class "Default")
      (node (ref "R5") (pin "2") (pinfunction "2_2") (pintype "passive"))
    )
    (net (code "27") (name "/RESETn") (class "Default")
      (node (ref "R6") (pin "2") (pinfunction "2_2") (pintype "passive"))
    )
    (net (code "28") (name "/RUSB-D_n") (class "Default")
      (node (ref "R28") (pin "1") (pinfunction "1_1") (pintype "passive"))
      (node (ref "U108") (pin "7") (pinfunction "DM_7") (pintype "bidirectional"))
      (node (ref "U109") (pin "9") (pinfunction "USBDM_9") (pintype "input"))
    )
    (net (code "29") (name "/RUSB-D_p") (class "Default")
      (node (ref "R24") (pin "1") (pinfunction "1_1") (pintype "passive"))
      (node (ref "U108") (pin "8") (pinfunction "DP_8") (pintype "bidirectional"))
      (node (ref "U109") (pin "8") (pinfunction "USBDP_8") (pintype "input"))
    )
    (net (code "30") (name "/USB-D_n") (class "Default")
      (node (ref "R28") (pin "2") (pinfunction "2_2") (pintype "passive"))
    )
    (net (code "31") (name "/USB-D_p") (class "Default")
      (node (ref "R24") (pin "2") (pinfunction "2_2") (pintype "passive"))
    )
    (net (code "35") (name "GND") (class "Default")
      (node (ref "C1") (pin "2") (pinfunction "2_2") (pintype "passive"))
      (node (ref "C10") (pin "2") (pinfunction "2_2") (pintype "passive"))
      (node (ref "C13") (pin "2") (pinfunction "2_2") (pintype "passive"))
      (node (ref "C14") (pin "2") (pinfunction "2_2") (pintype "passive"))
      (node (ref "C20") (pin "2") (pinfunction "2_2") (pintype "passive"))
      (node (ref "C21") (pin "2") (pinfunction "2_2") (pintype "passive"))
      (node (ref "C28") (pin "2") (pinfunction "2_2") (pintype "passive"))
      (node (ref "C3") (pin "2") (pinfunction "2_2") (pintype "passive"))
      (node (ref "C30") (pin "2") (pinfunction "2_2") (pintype "passive"))
      (node (ref "C31") (pin "2") (pinfunction "2_2") (pintype "passive"))
      (node (ref "C32") (pin "2") (pinfunction "2_2") (pintype "passive"))
      (node (ref "C33") (pin "2") (pinfunction "2_2") (pintype "passive"))
      (node (ref "C34") (pin "2") (pinfunction "2_2") (pintype "passive"))
      (node (ref "C35") (pin "2") (pinfunction "2_2") (pintype "passive"))
      (node (ref "C36") (pin "2") (pinfunction "2_2") (pintype "passive"))
      (node (ref "C37") (pin "2") (pinfunction "2_2") (pintype "passive"))
      (node (ref "C38") (pin "2") (pinfunction "2_2") (pintype "passive"))
      (node (ref "C41") (pin "2") (pinfunction "2_2") (pintype "passive"))
      (node (ref "C60") (pin "2") (pinfunction "2_2") (pintype "passive"))
      (node (ref "C61") (pin "2") (pinfunction "2_2") (pintype "passive"))
      (node (ref "R114") (pin "1") (pinfunction "1_1") (pintype "passive"))
      (node (ref "R84") (pin "1") (pinfunction "1_1") (pintype "passive"))
      (node (ref "R92") (pin "2") (pinfunction "2_2") (pintype "passive"))
      (node (ref "U10") (pin "5") (pinfunction "VSS_5") (pintype "power_in"))
      (node (ref "U10") (pin "9") (pinfunction "DAP_9") (pintype "power_in"))
      (node (ref "U108") (pin "1") (pinfunction "GND_1") (pintype "power_in"))
      (node (ref "U108") (pin "10") (pinfunction "AGND_10") (pintype "power_in"))
      (node (ref "U108") (pin "11") (pinfunction "GND_11") (pintype "power_in"))
      (node (ref "U108") (pin "13") (pinfunction "TEST_13") (pintype "input"))
      (node (ref "U108") (pin "15") (pinfunction "GND_15") (pintype "power_in"))
      (node (ref "U108") (pin "25") (pinfunction "GND_25") (pintype "power_in"))
      (node (ref "U108") (pin "35") (pinfunction "GND_35") (pintype "power_in"))
      (node (ref "U108") (pin "47") (pinfunction "GND_47") (pintype "power_in"))
      (node (ref "U108") (pin "5") (pinfunction "GND_5") (pintype "power_in"))
      (node (ref "U108") (pin "51") (pinfunction "GND_51") (pintype "power_in"))
      (node (ref "U109") (pin "13") (pinfunction "GND_13") (pintype "power_in"))
      (node (ref "U109") (pin "21") (pinfunction "GND_21") (pintype "power_in"))
      (node (ref "U109") (pin "3") (pinfunction "GND_3") (pintype "power_in"))
      (node (ref "X2") (pin "2") (pintype "passive"))
      (node (ref "X2") (pin "4") (pintype "passive"))
    )
    (net (code "36") (name "Net-(J117-Pad1)") (class "Default")
      (node (ref "J117") (pin "1") (pintype "passive"))
      (node (ref "R58") (pin "2") (pinfunction "2_2") (pintype "passive"))
    )
    (net (code "37") (name "Net-(J117-Pad2)") (class "Default")
      (node (ref "J117") (pin "2") (pintype "passive"))
      (node (ref "R59") (pin "2") (pinfunction "2_2") (pintype "passive"))
    )
    (net (code "38") (name "Net-(J117-Pad3)") (class "Default")
      (node (ref "J117") (pin "3") (pintype "passive"))
      (node (ref "R60") (pin "2") (pinfunction "2_2") (pintype "passive"))
    )
    (net (code "39") (name "Net-(J117-Pad4)") (class "Default")
      (node (ref "J117") (pin "4") (pintype "passive"))
      (node (ref "R61") (pin "2") (pinfunction "2_2") (pintype "passive"))
    )
    (net (code "40") (name "Net-(J117-Pad5)") (class "Default")
      (node (ref "J117") (pin "5") (pintype "passive"))
      (node (ref "R63") (pin "2") (pinfunction "2_2") (pintype "passive"))
    )
    (net (code "41") (name "Net-(J117-Pad6)") (class "Default")
      (node (ref "J117") (pin "6") (pintype "passive"))
      (node (ref "R64") (pin "2") (pinfunction "2_2") (pintype "passive"))
    )
    (net (code "42") (name "Net-(J117-Pad7)") (class "Default")
      (node (ref "J117") (pin "7") (pintype "passive"))
      (node (ref "R65") (pin "2") (pinfunction "2_2") (pintype "passive"))
    )
    (net (code "43") (name "Net-(J117-Pad8)") (class "Default")
      (node (ref "J117") (pin "8") (pintype "passive"))
      (node (ref "R66") (pin "2") (pinfunction "2_2") (pintype "passive"))
    )
    (net (code "44") (name "Net-(U10-DO)") (class "Default")
      (node (ref "R86") (pin "1") (pinfunction "1_1") (pintype "passive"))
      (node (ref "R90") (pin "2") (pinfunction "2_2") (pintype "passive"))
      (node (ref "U10") (pin "4") (pinfunction "DO_4") (pintype "tri_state"))
    )
    (net (code "45") (name "Net-(U10-ORG)") (class "Default")
      (node (ref "R114") (pin "2") (pinfunction "2_2") (pintype "passive"))
      (node (ref "R89") (pin "2") (pinfunction "2_2") (pintype "passive"))
      (node (ref "U10") (pin "6") (pinfunction "ORG_6") (pintype "input"))
    )
    (net (code "46") (name "Net-(U108-ADBUS0)") (class "Default")
      (node (ref "R1") (pin "1") (pinfunction "1_1") (pintype "passive"))
      (node (ref "U108") (pin "16") (pinfunction "ADBUS0_16") (pintype "bidirectional"))
    )
    (net (code "47") (name "Net-(U108-ADBUS1)") (class "Default")
      (node (ref "R3") (pin "1") (pinfunction "1_1") (pintype "passive"))
      (node (ref "U108") (pin "17") (pinfunction "ADBUS1_17") (pintype "bidirectional"))
    )
    (net (code "48") (name "Net-(U108-ADBUS2)") (class "Default")
      (node (ref "R4") (pin "1") (pinfunction "1_1") (pintype "passive"))
      (node (ref "U108") (pin "18") (pinfunction "ADBUS2_18") (pintype "bidirectional"))
    )
    (net (code "49") (name "Net-(U108-ADBUS3)") (class "Default")
      (node (ref "R5") (pin "1") (pinfunction "1_1") (pintype "passive"))
      (node (ref "U108") (pin "19") (pinfunction "ADBUS3_19") (pintype "bidirectional"))
    )
    (net (code "50") (name "Net-(U108-ADBUS5)") (class "Default")
      (node (ref "R6") (pin "1") (pinfunction "1_1") (pintype "passive"))
      (node (ref "U108") (pin "22") (pinfunction "ADBUS5_22") (pintype "bidirectional"))
    )
    (net (code "51") (name "Net-(U108-ADBUS6)") (class "Default")
      (node (ref "R7") (pin "1") (pinfunction "1_1") (pintype "passive"))
      (node (ref "U108") (pin "23") (pinfunction "ADBUS6_23") (pintype "bidirectional"))
    )
    (net (code "52") (name "Net-(U108-BDBUS0)") (class "Default")
      (node (ref "R8") (pin "1") (pinfunction "1_1") (pintype "passive"))
      (node (ref "U108") (pin "26") (pinfunction "BDBUS0_26") (pintype "bidirectional"))
    )
    (net (code "53") (name "Net-(U108-BDBUS1)") (class "Default")
      (node (ref "R9") (pin "1") (pinfunction "1_1") (pintype "passive"))
      (node (ref "U108") (pin "27") (pinfunction "BDBUS1_27") (pintype "bidirectional"))
    )
    (net (code "54") (name "Net-(U108-BDBUS2)") (class "Default")
      (node (ref "R37") (pin "1") (pinfunction "1_1") (pintype "passive"))
      (node (ref "U108") (pin "28") (pinfunction "BDBUS2_28") (pintype "bidirectional"))
    )
    (net (code "55") (name "Net-(U108-BDBUS3)") (class "Default")
      (node (ref "R38") (pin "1") (pinfunction "1_1") (pintype "passive"))
      (node (ref "U108") (pin "29") (pinfunction "BDBUS3_29") (pintype "bidirectional"))
    )
    (net (code "56") (name "Net-(U108-BDBUS4)") (class "Default")
      (node (ref "R41") (pin "1") (pinfunction "1_1") (pintype "passive"))
      (node (ref "U108") (pin "30") (pinfunction "BDBUS4_30") (pintype "bidirectional"))
    )
    (net (code "57") (name "Net-(U108-BDBUS5)") (class "Default")
      (node (ref "R42") (pin "1") (pinfunction "1_1") (pintype "passive"))
      (node (ref "U108") (pin "32") (pinfunction "BDBUS5_32") (pintype "bidirectional"))
    )
    (net (code "58") (name "Net-(U108-CDBUS0)") (class "Default")
      (node (ref "R52") (pin "1") (pinfunction "1_1") (pintype "passive"))
      (node (ref "U108") (pin "38") (pinfunction "CDBUS0_38") (pintype "bidirectional"))
      (node (ref "U109") (pin "17") (pinfunction "TXD_17") (pintype "output"))
    )
    (net (code "59") (name "Net-(U108-CDBUS1)") (class "Default")
      (node (ref "R53") (pin "1") (pinfunction "1_1") (pintype "passive"))
      (node (ref "U108") (pin "39") (pinfunction "CDBUS1_39") (pintype "bidirectional"))
      (node (ref "U109") (pin "1") (pinfunction "RXD_1") (pintype "input"))
    )
    (net (code "60") (name "Net-(U108-CDBUS2)") (class "Default")
      (node (ref "R54") (pin "1") (pinfunction "1_1") (pintype "passive"))
      (node (ref "U108") (pin "40") (pinfunction "CDBUS2_40") (pintype "bidirectional"))
      (node (ref "U109") (pin "19") (pinfunction "~{RTS}_19") (pintype "output"))
    )
    (net (code "61") (name "Net-(U108-CDBUS3)") (class "Default")
      (node (ref "R55") (pin "1") (pinfunction "1_1") (pintype "passive"))
      (node (ref "U108") (pin "41") (pinfunction "CDBUS3_41") (pintype "bidirectional"))
      (node (ref "U109") (pin "6") (pinfunction "~{CTS}_6") (pintype "input"))
    )
    (net (code "62") (name "Net-(U108-CDBUS4)") (class "Default")
      (node (ref "R56") (pin "1") (pinfunction "1_1") (pintype "passive"))
      (node (ref "U108") (pin "43") (pinfunction "CDBUS4_43") (pintype "bidirectional"))
      (node (ref "U109") (pin "18") (pinfunction "~{DTR}_18") (pintype "output"))
    )
    (net (code "63") (name "Net-(U108-CDBUS5)") (class "Default")
      (node (ref "R57") (pin "1") (pinfunction "1_1") (pintype "passive"))
      (node (ref "U108") (pin "44") (pinfunction "CDBUS5_44") (pintype "bidirectional"))
      (node (ref "U109") (pin "4") (pinfunction "~{DSR}_4") (pintype "input"))
    )
    (net (code "64") (name "Net-(U108-DDBUS0)") (class "Default")
      (node (ref "R58") (pin "1") (pinfunction "1_1") (pintype "passive"))
      (node (ref "U108") (pin "48") (pinfunction "DDBUS0_48") (pintype "bidirectional"))
    )
    (net (code "65") (name "Net-(U108-DDBUS1)") (class "Default")
      (node (ref "R59") (pin "1") (pinfunction "1_1") (pintype "passive"))
      (node (ref "U108") (pin "52") (pinfunction "DDBUS1_52") (pintype "bidirectional"))
    )
    (net (code "66") (name "Net-(U108-DDBUS2)") (class "Default")
      (node (ref "R60") (pin "1") (pinfunction "1_1") (pintype "passive"))
      (node (ref "U108") (pin "53") (pinfunction "DDBUS2_53") (pintype "bidirectional"))
    )
    (net (code "67") (name "Net-(U108-DDBUS3)") (class "Default")
      (node (ref "R61") (pin "1") (pinfunction "1_1") (pintype "passive"))
      (node (ref "U108") (pin "54") (pinfunction "DDBUS3_54") (pintype "bidirectional"))
    )
    (net (code "68") (name "Net-(U108-DDBUS4)") (class "Default")
      (node (ref "R63") (pin "1") (pinfunction "1_1") (pintype "passive"))
      (node (ref "U108") (pin "55") (pinfunction "DDBUS4_55") (pintype "bidirectional"))
    )
    (net (code "69") (name "Net-(U108-DDBUS5)") (class "Default")
      (node (ref "R64") (pin "1") (pinfunction "1_1") (pintype "passive"))
      (node (ref "U108") (pin "57") (pinfunction "DDBUS5_57") (pintype "bidirectional"))
    )
    (net (code "70") (name "Net-(U108-DDBUS6)") (class "Default")
      (node (ref "R65") (pin "1") (pinfunction "1_1") (pintype "passive"))
      (node (ref "U108") (pin "58") (pinfunction "DDBUS6_58") (pintype "bidirectional"))
    )
    (net (code "71") (name "Net-(U108-DDBUS7)") (class "Default")
      (node (ref "R66") (pin "1") (pinfunction "1_1") (pintype "passive"))
      (node (ref "U108") (pin "59") (pinfunction "DDBUS7_59") (pintype "bidirectional"))
    )
    (net (code "72") (name "Net-(U108-OSCI)") (class "Default")
      (node (ref "C36") (pin "1") (pinfunction "1_1") (pintype "passive"))
      (node (ref "U108") (pin "2") (pinfunction "OSCI_2") (pintype "input"))
      (node (ref "X2") (pin "1") (pintype "passive"))
    )
    (net (code "73") (name "Net-(U108-OSCO)") (class "Default")
      (node (ref "C37") (pin "1") (pinfunction "1_1") (pintype "passive"))
      (node (ref "U108") (pin "3") (pinfunction "OSCO_3") (pintype "output"))
      (node (ref "X2") (pin "3") (pintype "passive"))
    )
    (net (code "74") (name "Net-(U108-REF)") (class "Default")
      (node (ref "R84") (pin "2") (pinfunction "2_2") (pintype "passive"))
      (node (ref "U108") (pin "6") (pinfunction "REF_6") (pintype "passive"))
    )
    (net (code "75") (name "Net-(U108-VPHY)") (class "Default")
      (node (ref "C10") (pin "1") (pinfunction "1_1") (pintype "passive"))
      (node (ref "C30") (pin "1") (pinfunction "1_1") (pintype "passive"))
      (node (ref "F4") (pin "2") (pinfunction "2_2") (pintype "passive"))
      (node (ref "U108") (pin "4") (pinfunction "VPHY_4") (pintype "power_in"))
    )
    (net (code "76") (name "Net-(U108-VPLL)") (class "Default")
      (node (ref "C14") (pin "1") (pinfunction "1_1") (pintype "passive"))
      (node (ref "C31") (pin "1") (pinfunction "1_1") (pintype "passive"))
      (node (ref "F3") (pin "2") (pinfunction "2_2") (pintype "passive"))
      (node (ref "U108") (pin "9") (pinfunction "VPLL_9") (pintype "power_in"))
    )
    (net (code "77") (name "Net-(U108-VREGOUT)") (class "Default")
      (node (ref "C32") (pin "1") (pinfunction "1_1") (pintype "passive"))
      (node (ref "C33") (pin "1") (pinfunction "1_1") (pintype "passive"))
      (node (ref "C35") (pin "1") (pinfunction "1_1") (pintype "passive"))
      (node (ref "C61") (pin "1") (pinfunction "1_1") (pintype "passive"))
      (node (ref "U108") (pin "12") (pinfunction "VCORE_12") (pintype "power_in"))
      (node (ref "U108") (pin "37") (pinfunction "VCORE_37") (pintype "power_in"))
      (node (ref "U108") (pin "49") (pinfunction "VREGOUT_49") (pintype "power_in"))
      (node (ref "U108") (pin "64") (pinfunction "VCORE_64") (pintype "power_in"))
    )
    (net (code "78") (name "Net-(U108-~{RESET})") (class "Default")
      (node (ref "R85") (pin "2") (pinfunction "2_2") (pintype "passive"))
      (node (ref "U108") (pin "14") (pinfunction "~{RESET}_14") (pintype "input"))
    )
    (net (code "79") (name "Net-(U109-3V3OUT)") (class "Default")
      (node (ref "C1") (pin "1") (pinfunction "1_1") (pintype "passive"))
      (node (ref "C3") (pin "1") (pinfunction "1_1") (pintype "passive"))
      (node (ref "C34") (pin "1") (pinfunction "1_1") (pintype "passive"))
      (node (ref "C38") (pin "1") (pinfunction "1_1") (pintype "passive"))
      (node (ref "F5") (pin "2") (pinfunction "2_2") (pintype "passive"))
      (node (ref "U109") (pin "10") (pinfunction "3V3OUT_10") (pintype "input"))
      (node (ref "U109") (pin "11") (pinfunction "~{RESET}_11") (pintype "input"))
      (node (ref "U109") (pin "12") (pinfunction "VCC_12") (pintype "power_in"))
      (node (ref "U109") (pin "20") (pinfunction "VCCIO_20") (pintype "power_in"))
    )
    (net (code "80") (name "Net-(U109-CBUS3)") (class "Default")
      (node (ref "R91") (pin "1") (pinfunction "1_1") (pintype "passive"))
      (node (ref "R92") (pin "1") (pinfunction "1_1") (pintype "passive"))
      (node (ref "U109") (pin "16") (pinfunction "CBUS3_16") (pintype "bidirectional"))
    )
    (net (code "81") (name "unconnected-(U10-NC-Pad7)") (class "Default")
      (node (ref "U10") (pin "7") (pinfunction "NC_7") (pintype "passive+no_connect"))
    )
    (net (code "82") (name "unconnected-(U108-ADBUS4-Pad21)") (class "Default")
      (node (ref "U108") (pin "21") (pinfunction "ADBUS4_21") (pintype "bidirectional+no_connect"))
    )
    (net (code "83") (name "unconnected-(U108-ADBUS7-Pad24)") (class "Default")
      (node (ref "U108") (pin "24") (pinfunction "ADBUS7_24") (pintype "bidirectional+no_connect"))
    )
    (net (code "84") (name "unconnected-(U108-BDBUS6-Pad33)") (class "Default")
      (node (ref "U108") (pin "33") (pinfunction "BDBUS6_33") (pintype "bidirectional+no_connect"))
    )
    (net (code "85") (name "unconnected-(U108-BDBUS7-Pad34)") (class "Default")
      (node (ref "U108") (pin "34") (pinfunction "BDBUS7_34") (pintype "bidirectional+no_connect"))
    )
    (net (code "86") (name "unconnected-(U108-CDBUS6-Pad45)") (class "Default")
      (node (ref "U108") (pin "45") (pinfunction "CDBUS6_45") (pintype "bidirectional+no_connect"))
    )
    (net (code "87") (name "unconnected-(U108-CDBUS7-Pad46)") (class "Default")
      (node (ref "U108") (pin "46") (pinfunction "CDBUS7_46") (pintype "bidirectional+no_connect"))
    )
    (net (code "88") (name "unconnected-(U108-~{PWREN}-Pad60)") (class "Default")
      (node (ref "U108") (pin "60") (pinfunction "~{PWREN}_60") (pintype "output+no_connect"))
    )
    (net (code "89") (name "unconnected-(U108-~{SUSPEND}-Pad36)") (class "Default")
      (node (ref "U108") (pin "36") (pinfunction "~{SUSPEND}_36") (pintype "output+no_connect"))
    )
    (net (code "90") (name "unconnected-(U109-CBUS0-Pad15)") (class "Default")
      (node (ref "U109") (pin "15") (pinfunction "CBUS0_15") (pintype "bidirectional+no_connect"))
    )
    (net (code "91") (name "unconnected-(U109-CBUS1-Pad14)") (class "Default")
      (node (ref "U109") (pin "14") (pinfunction "CBUS1_14") (pintype "bidirectional+no_connect"))
    )
    (net (code "92") (name "unconnected-(U109-CBUS2-Pad7)") (class "Default")
      (node (ref "U109") (pin "7") (pinfunction "CBUS2_7") (pintype "bidirectional+no_connect"))
    )
    (net (code "93") (name "unconnected-(U109-~{DCD}-Pad5)") (class "Default")
      (node (ref "U109") (pin "5") (pinfunction "~{DCD}_5") (pintype "input+no_connect"))
    )
    (net (code "94") (name "unconnected-(U109-~{RI}-Pad2)") (class "Default")
      (node (ref "U109") (pin "2") (pinfunction "~{RI}_2") (pintype "input+no_connect"))
    )
  )
)
